# 30s-60s.net
KiCad netlist of a schematic drawn in Altium Designer
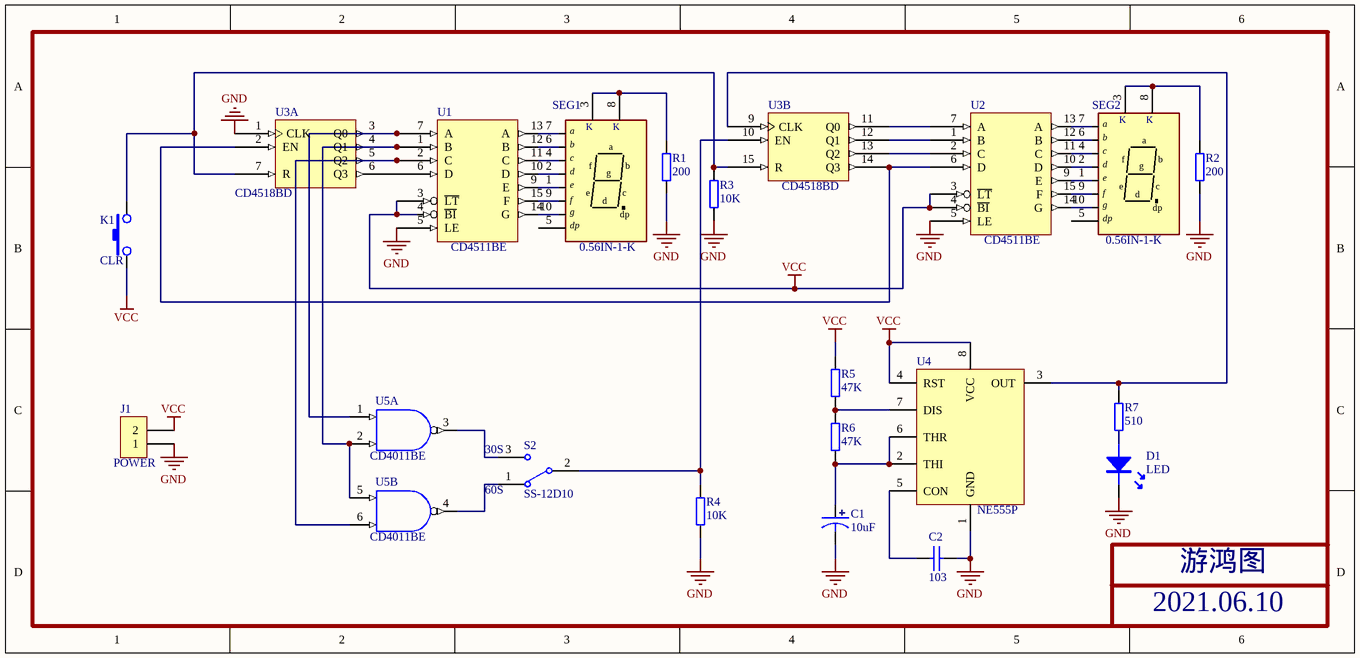
[diagram p0: 30s-60s计时器.SchDoc]

(export (version "E")
  (design (tool "Eeschema 10.0.6"))
  (components
    (comp (ref "C1")
      (value "10uF")
      (footprint "DIP-EC1.5X4X8")
      (description "直插电解电容")
      (libsource (lib "电容") (part "DIP_ECAP"))
    )
    (comp (ref "C2")
      (value "103")
      (footprint "RAD-0.2")
      (description "无极性电容")
      (libsource (lib "电容") (part "CAP"))
    )
    (comp (ref "D1") (value "LED") (footprint "LED3-RED") (libsource (lib "LED") (part "LED")))
    (comp (ref "J1")
      (value "POWER")
      (footprint "CONN-TH_2P-P5.08_DB128L-5.08-2P")
      (libsource (lib "排针") (part "Pin HDR1X2"))
    )
    (comp (ref "K1") (value "CLR") (footprint "DIP-6X6X6") (libsource (lib "轻触开关") (part "KEY")))
    (comp (ref "R1")
      (value "200")
      (footprint "AXIAL0.4")
      (description "电阻")
      (libsource (lib "自建lib") (part "RES"))
    )
    (comp (ref "R2")
      (value "200")
      (footprint "AXIAL0.4")
      (description "电阻")
      (libsource (lib "自建lib") (part "RES"))
    )
    (comp (ref "R3")
      (value "10K")
      (footprint "AXIAL0.4")
      (description "电阻")
      (libsource (lib "自建lib") (part "RES"))
    )
    (comp (ref "R4")
      (value "10K")
      (footprint "AXIAL0.4")
      (description "电阻")
      (libsource (lib "自建lib") (part "RES"))
    )
    (comp (ref "R5")
      (value "47K")
      (footprint "AXIAL0.4")
      (description "电阻")
      (libsource (lib "自建lib") (part "RES"))
    )
    (comp (ref "R6")
      (value "47K")
      (footprint "AXIAL0.4")
      (description "电阻")
      (libsource (lib "自建lib") (part "RES"))
    )
    (comp (ref "R7")
      (value "510")
      (footprint "AXIAL0.4")
      (description "电阻")
      (libsource (lib "自建lib") (part "RES"))
    )
    (comp (ref "S2")
      (value "SS-12D10")
      (footprint "Pin HDR1X3/2.54mm-S")
      (libsource (lib "电源开关") (part "SS-12D10"))
    )
    (comp (ref "SEG1")
      (value "0.56IN-1-K")
      (footprint "0.56IN-1P")
      (description "1位0.56寸共阴数码管")
      (libsource (lib "数码管") (part "0.56IN-1-K"))
    )
    (comp (ref "SEG2")
      (value "0.56IN-1-K")
      (footprint "0.56IN-1P")
      (description "1位0.56寸共阴数码管")
      (libsource (lib "数码管") (part "0.56IN-1-K"))
    )
    (comp (ref "U1")
      (value "CD4511BE")
      (footprint "DIP-16")
      (libsource (lib "Protel DOS Schematic 4000 CMOS") (part "4511"))
    )
    (comp (ref "U2")
      (value "CD4511BE")
      (footprint "DIP-16")
      (libsource (lib "Protel DOS Schematic 4000 CMOS") (part "4511"))
    )
    (comp (ref "U3")
      (value "CD4518BD")
      (footprint "DIP-16")
      (libsource (lib "Protel DOS Schematic 4000 CMOS") (part "4518"))
    )
    (comp (ref "U4") (value "NE555P") (footprint "DIP8") (libsource (lib "未分类IC") (part "NE555")))
    (comp (ref "U5")
      (value "CD4011BE")
      (footprint "DIP-14")
      (description "Quad 2-Input NAND Gate")
      (libsource (lib "CMOS") (part "4011"))
    )
  )
  (nets
    (net (code "1") (name "GND") (class "Default")
      (node (ref "C1") (pin "2") (pinfunction "2_2") (pintype "passive"))
      (node (ref "C2") (pin "2") (pinfunction "2_2") (pintype "passive"))
      (node (ref "D1") (pin "K") (pinfunction "K_K") (pintype "passive"))
      (node (ref "J1") (pin "1") (pinfunction "1_1") (pintype "passive"))
      (node (ref "R1") (pin "2") (pinfunction "2_2") (pintype "passive"))
      (node (ref "R2") (pin "2") (pinfunction "2_2") (pintype "passive"))
      (node (ref "R3") (pin "1") (pinfunction "1_1") (pintype "passive"))
      (node (ref "R4") (pin "1") (pinfunction "1_1") (pintype "passive"))
      (node (ref "U1") (pin "5") (pinfunction "LE_5") (pintype "input"))
      (node (ref "U1") (pin "8") (pinfunction "GND_8") (pintype "power_in"))
      (node (ref "U2") (pin "5") (pinfunction "LE_5") (pintype "input"))
      (node (ref "U2") (pin "8") (pinfunction "GND_8") (pintype "power_in"))
      (node (ref "U3") (pin "1") (pinfunction "CLK_1") (pintype "input"))
      (node (ref "U3") (pin "8") (pinfunction "GND_8") (pintype "power_in"))
      (node (ref "U4") (pin "1") (pinfunction "GND_1") (pintype "passive"))
      (node (ref "U5") (pin "7") (pinfunction "GND_7") (pintype "power_in"))
    )
    (net (code "2") (name "Net-(D1-PadA)") (class "Default")
      (node (ref "D1") (pin "A") (pinfunction "A_A") (pintype "passive"))
      (node (ref "R7") (pin "1") (pinfunction "1_1") (pintype "passive"))
    )
    (net (code "3") (name "Net-(SEG1-Pad2)") (class "Default")
      (node (ref "SEG1") (pin "2") (pinfunction "2_2") (pintype "passive"))
      (node (ref "U1") (pin "10") (pinfunction "D_10") (pintype "output"))
    )
    (net (code "4") (name "Net-(SEG1-Pad4)") (class "Default")
      (node (ref "SEG1") (pin "4") (pinfunction "4_4") (pintype "passive"))
      (node (ref "U1") (pin "11") (pinfunction "C_11") (pintype "output"))
    )
    (net (code "5") (name "Net-(SEG1-Pad6)") (class "Default")
      (node (ref "SEG1") (pin "6") (pinfunction "6_6") (pintype "passive"))
      (node (ref "U1") (pin "12") (pinfunction "B_12") (pintype "output"))
    )
    (net (code "6") (name "Net-(SEG1-Pad7)") (class "Default")
      (node (ref "SEG1") (pin "7") (pinfunction "7_7") (pintype "passive"))
      (node (ref "U1") (pin "13") (pinfunction "A_13") (pintype "output"))
    )
    (net (code "7") (name "Net-(SEG1-VCC)") (class "Default")
      (node (ref "R1") (pin "1") (pinfunction "1_1") (pintype "passive"))
      (node (ref "SEG1") (pin "3") (pinfunction "VCC_3") (pintype "passive"))
      (node (ref "SEG1") (pin "8") (pinfunction "8_8") (pintype "passive"))
    )
    (net (code "8") (name "Net-(SEG2-Pad2)") (class "Default")
      (node (ref "SEG2") (pin "2") (pinfunction "2_2") (pintype "passive"))
      (node (ref "U2") (pin "10") (pinfunction "D_10") (pintype "output"))
    )
    (net (code "9") (name "Net-(SEG2-Pad4)") (class "Default")
      (node (ref "SEG2") (pin "4") (pinfunction "4_4") (pintype "passive"))
      (node (ref "U2") (pin "11") (pinfunction "C_11") (pintype "output"))
    )
    (net (code "10") (name "Net-(SEG2-Pad6)") (class "Default")
      (node (ref "SEG2") (pin "6") (pinfunction "6_6") (pintype "passive"))
      (node (ref "U2") (pin "12") (pinfunction "B_12") (pintype "output"))
    )
    (net (code "11") (name "Net-(SEG2-Pad7)") (class "Default")
      (node (ref "SEG2") (pin "7") (pinfunction "7_7") (pintype "passive"))
      (node (ref "U2") (pin "13") (pinfunction "A_13") (pintype "output"))
    )
    (net (code "12") (name "Net-(SEG2-VCC)") (class "Default")
      (node (ref "R2") (pin "1") (pinfunction "1_1") (pintype "passive"))
      (node (ref "SEG2") (pin "3") (pinfunction "VCC_3") (pintype "passive"))
      (node (ref "SEG2") (pin "8") (pinfunction "8_8") (pintype "passive"))
    )
    (net (code "13") (name "Net-(U1-E)") (class "Default")
      (node (ref "SEG1") (pin "1") (pinfunction "1_1") (pintype "passive"))
      (node (ref "U1") (pin "9") (pinfunction "E_9") (pintype "output"))
    )
    (net (code "14") (name "Net-(U1-F)") (class "Default")
      (node (ref "SEG1") (pin "9") (pinfunction "9_9") (pintype "passive"))
      (node (ref "U1") (pin "15") (pinfunction "F_15") (pintype "output"))
    )
    (net (code "15") (name "Net-(U1-G)") (class "Default")
      (node (ref "SEG1") (pin "10") (pinfunction "10_10") (pintype "passive"))
      (node (ref "U1") (pin "14") (pinfunction "G_14") (pintype "output"))
    )
    (net (code "16") (name "Net-(U2-E)") (class "Default")
      (node (ref "SEG2") (pin "1") (pinfunction "1_1") (pintype "passive"))
      (node (ref "U2") (pin "9") (pinfunction "E_9") (pintype "output"))
    )
    (net (code "17") (name "Net-(U2-F)") (class "Default")
      (node (ref "SEG2") (pin "9") (pinfunction "9_9") (pintype "passive"))
      (node (ref "U2") (pin "15") (pinfunction "F_15") (pintype "output"))
    )
    (net (code "18") (name "Net-(U2-G)") (class "Default")
      (node (ref "SEG2") (pin "10") (pinfunction "10_10") (pintype "passive"))
      (node (ref "U2") (pin "14") (pinfunction "G_14") (pintype "output"))
    )
    (net (code "19") (name "Net-(U3A-EN)") (class "Default")
      (node (ref "U2") (pin "6") (pinfunction "D_6") (pintype "input"))
      (node (ref "U3") (pin "14") (pinfunction "Q3_14") (pintype "output"))
      (node (ref "U3") (pin "2") (pinfunction "EN_2") (pintype "input"))
    )
    (net (code "20") (name "Net-(U3A-Q0)") (class "Default")
      (node (ref "U1") (pin "7") (pinfunction "A_7") (pintype "input"))
      (node (ref "U3") (pin "3") (pinfunction "Q0_3") (pintype "output"))
      (node (ref "U5") (pin "1") (pinfunction "A_1") (pintype "input"))
    )
    (net (code "21") (name "Net-(U3A-Q1)") (class "Default")
      (node (ref "U1") (pin "1") (pinfunction "B_1") (pintype "input"))
      (node (ref "U3") (pin "4") (pinfunction "Q1_4") (pintype "output"))
      (node (ref "U5") (pin "2") (pinfunction "B_2") (pintype "input"))
      (node (ref "U5") (pin "5") (pinfunction "A_5") (pintype "input"))
    )
    (net (code "22") (name "Net-(U3A-Q2)") (class "Default")
      (node (ref "U1") (pin "2") (pinfunction "C_2") (pintype "input"))
      (node (ref "U3") (pin "5") (pinfunction "Q2_5") (pintype "output"))
      (node (ref "U5") (pin "6") (pinfunction "B_6") (pintype "input"))
    )
    (net (code "23") (name "Net-(U3A-Q3)") (class "Default")
      (node (ref "U1") (pin "6") (pinfunction "D_6") (pintype "input"))
      (node (ref "U3") (pin "6") (pinfunction "Q3_6") (pintype "output"))
    )
    (net (code "24") (name "Net-(U3A-R)") (class "Default")
      (node (ref "K1") (pin "3") (pinfunction "3_3") (pintype "passive"))
      (node (ref "R3") (pin "2") (pinfunction "2_2") (pintype "passive"))
      (node (ref "U3") (pin "15") (pinfunction "R_15") (pintype "input"))
      (node (ref "U3") (pin "7") (pinfunction "R_7") (pintype "input"))
    )
    (net (code "25") (name "Net-(U3B-CLK)") (class "Default")
      (node (ref "R7") (pin "2") (pinfunction "2_2") (pintype "passive"))
      (node (ref "U3") (pin "9") (pinfunction "CLK_9") (pintype "input"))
      (node (ref "U4") (pin "3") (pinfunction "OUT_3") (pintype "passive"))
    )
    (net (code "26") (name "Net-(U3B-EN)") (class "Default")
      (node (ref "R4") (pin "2") (pinfunction "2_2") (pintype "passive"))
      (node (ref "S2") (pin "2") (pinfunction "2_2") (pintype "passive"))
      (node (ref "U3") (pin "10") (pinfunction "EN_10") (pintype "input"))
    )
    (net (code "27") (name "Net-(U3B-Q0)") (class "Default")
      (node (ref "U2") (pin "7") (pinfunction "A_7") (pintype "input"))
      (node (ref "U3") (pin "11") (pinfunction "Q0_11") (pintype "output"))
    )
    (net (code "28") (name "Net-(U3B-Q1)") (class "Default")
      (node (ref "U2") (pin "1") (pinfunction "B_1") (pintype "input"))
      (node (ref "U3") (pin "12") (pinfunction "Q1_12") (pintype "output"))
    )
    (net (code "29") (name "Net-(U3B-Q2)") (class "Default")
      (node (ref "U2") (pin "2") (pinfunction "C_2") (pintype "input"))
      (node (ref "U3") (pin "13") (pinfunction "Q2_13") (pintype "output"))
    )
    (net (code "30") (name "Net-(U4-CON)") (class "Default")
      (node (ref "C2") (pin "1") (pinfunction "1_1") (pintype "passive"))
      (node (ref "U4") (pin "5") (pinfunction "CON_5") (pintype "passive"))
    )
    (net (code "31") (name "Net-(U4-DIS)") (class "Default")
      (node (ref "R5") (pin "1") (pinfunction "1_1") (pintype "passive"))
      (node (ref "R6") (pin "2") (pinfunction "2_2") (pintype "passive"))
      (node (ref "U4") (pin "7") (pinfunction "DIS_7") (pintype "passive"))
    )
    (net (code "32") (name "Net-(U4-THI)") (class "Default")
      (node (ref "C1") (pin "1") (pinfunction "1_1") (pintype "passive"))
      (node (ref "R6") (pin "1") (pinfunction "1_1") (pintype "passive"))
      (node (ref "U4") (pin "2") (pinfunction "THI_2") (pintype "passive"))
      (node (ref "U4") (pin "6") (pinfunction "THR_6") (pintype "passive"))
    )
    (net (code "33") (name "Net-(U5A-Y)") (class "Default")
      (node (ref "S2") (pin "3") (pinfunction "3_3") (pintype "passive"))
      (node (ref "U5") (pin "3") (pinfunction "Y_3") (pintype "output"))
    )
    (net (code "34") (name "Net-(U5B-Y)") (class "Default")
      (node (ref "S2") (pin "1") (pinfunction "1_1") (pintype "passive"))
      (node (ref "U5") (pin "4") (pinfunction "Y_4") (pintype "output"))
    )
    (net (code "35") (name "VCC") (class "Default")
      (node (ref "J1") (pin "2") (pinfunction "2_2") (pintype "passive"))
      (node (ref "K1") (pin "1") (pinfunction "1_1") (pintype "passive"))
      (node (ref "R5") (pin "2") (pinfunction "2_2") (pintype "passive"))
      (node (ref "U1") (pin "16") (pinfunction "VCC_16") (pintype "power_in"))
      (node (ref "U1") (pin "3") (pinfunction "~{LT}_3") (pintype "input"))
      (node (ref "U1") (pin "4") (pinfunction "~{BI}_4") (pintype "input"))
      (node (ref "U2") (pin "16") (pinfunction "VCC_16") (pintype "power_in"))
      (node (ref "U2") (pin "3") (pinfunction "~{LT}_3") (pintype "input"))
      (node (ref "U2") (pin "4") (pinfunction "~{BI}_4") (pintype "input"))
      (node (ref "U3") (pin "16") (pinfunction "VCC_16") (pintype "power_in"))
      (node (ref "U4") (pin "4") (pinfunction "RST_4") (pintype "passive"))
      (node (ref "U4") (pin "8") (pinfunction "VCC_8") (pintype "passive"))
    )
    (net (code "36") (name "VDD") (class "Default")
      (node (ref "U5") (pin "14") (pinfunction "VDD_14") (pintype "power_in"))
    )
    (net (code "37") (name "unconnected-(SEG1-Pad5)") (class "Default")
      (node (ref "SEG1") (pin "5") (pinfunction "5_5") (pintype "passive"))
    )
    (net (code "38") (name "unconnected-(SEG2-Pad5)") (class "Default")
      (node (ref "SEG2") (pin "5") (pinfunction "5_5") (pintype "passive"))
    )
  )
)
